# board1.net
KiCad netlist of a schematic drawn in EAGLE
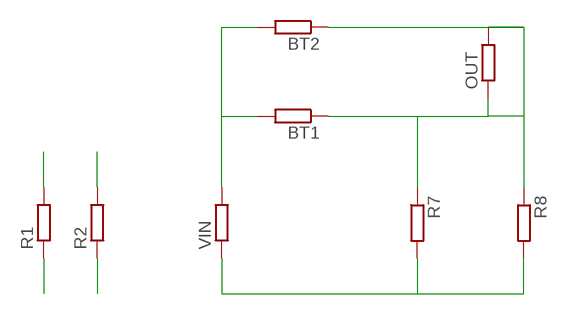
[diagram p0: schematic, sheet 1]

(export (version "E")
  (design (tool "Eeschema 10.0.6"))
  (components
    (comp (ref "BT1")
      (value "R-EU_0204/2V")
      (footprint "eagle-import:0204V")
      (libsource (lib "eagle-import") (part "resistor_R-EU_0204/2V"))
    )
    (comp (ref "BT2")
      (value "R-EU_0204/2V")
      (footprint "eagle-import:0204V")
      (libsource (lib "eagle-import") (part "resistor_R-EU_0204/2V"))
    )
    (comp (ref "OUT")
      (value "R-EU_0204/5")
      (footprint "eagle-import:0204_5")
      (libsource (lib "eagle-import") (part "R-EU_0204/5"))
    )
    (comp (ref "R1")
      (value "R-EU_0204/2V")
      (footprint "eagle-import:0204V")
      (libsource (lib "eagle-import") (part "resistor_R-EU_0204/2V"))
    )
    (comp (ref "R2")
      (value "R-EU_0204/2V")
      (footprint "eagle-import:0204V")
      (libsource (lib "eagle-import") (part "resistor_R-EU_0204/2V"))
    )
    (comp (ref "R7")
      (value "R-EU_0204/2V")
      (footprint "eagle-import:0204V")
      (libsource (lib "eagle-import") (part "resistor_R-EU_0204/2V"))
    )
    (comp (ref "R8")
      (value "R-EU_0204/2V")
      (footprint "eagle-import:0204V")
      (libsource (lib "eagle-import") (part "resistor_R-EU_0204/2V"))
    )
    (comp (ref "VIN")
      (value "R-EU_0204/2V")
      (footprint "eagle-import:0204V")
      (libsource (lib "eagle-import") (part "resistor_R-EU_0204/2V"))
    )
  )
  (nets
    (net (code "1") (name "Net-(BT1-Pad1)") (class "Default")
      (node (ref "BT1") (pin "1") (pinfunction "1_1") (pintype "passive"))
      (node (ref "OUT") (pin "1") (pinfunction "1_1") (pintype "passive"))
      (node (ref "R7") (pin "1") (pinfunction "1_1") (pintype "passive"))
    )
    (net (code "2") (name "Net-(BT1-Pad2)") (class "Default")
      (node (ref "BT1") (pin "2") (pinfunction "2_2") (pintype "passive"))
      (node (ref "BT2") (pin "2") (pinfunction "2_2") (pintype "passive"))
      (node (ref "VIN") (pin "2") (pinfunction "2_2") (pintype "passive"))
    )
    (net (code "3") (name "Net-(BT2-Pad1)") (class "Default")
      (node (ref "BT2") (pin "1") (pinfunction "1_1") (pintype "passive"))
      (node (ref "OUT") (pin "2") (pinfunction "2_2") (pintype "passive"))
      (node (ref "R8") (pin "1") (pinfunction "1_1") (pintype "passive"))
    )
    (net (code "4") (name "Net-(R7-Pad2)") (class "Default")
      (node (ref "R7") (pin "2") (pinfunction "2_2") (pintype "passive"))
      (node (ref "R8") (pin "2") (pinfunction "2_2") (pintype "passive"))
      (node (ref "VIN") (pin "1") (pinfunction "1_1") (pintype "passive"))
    )
    (net (code "5") (name "unconnected-(R1-Pad1)") (class "Default")
      (node (ref "R1") (pin "1") (pinfunction "1_1") (pintype "passive"))
    )
    (net (code "6") (name "unconnected-(R1-Pad2)") (class "Default")
      (node (ref "R1") (pin "2") (pinfunction "2_2") (pintype "passive"))
    )
    (net (code "7") (name "unconnected-(R2-Pad1)") (class "Default")
      (node (ref "R2") (pin "1") (pinfunction "1_1") (pintype "passive"))
    )
    (net (code "8") (name "unconnected-(R2-Pad2)") (class "Default")
      (node (ref "R2") (pin "2") (pinfunction "2_2") (pintype "passive"))
    )
  )
)
